# Rpi-CAN.net
KiCad netlist of a schematic drawn in EAGLE
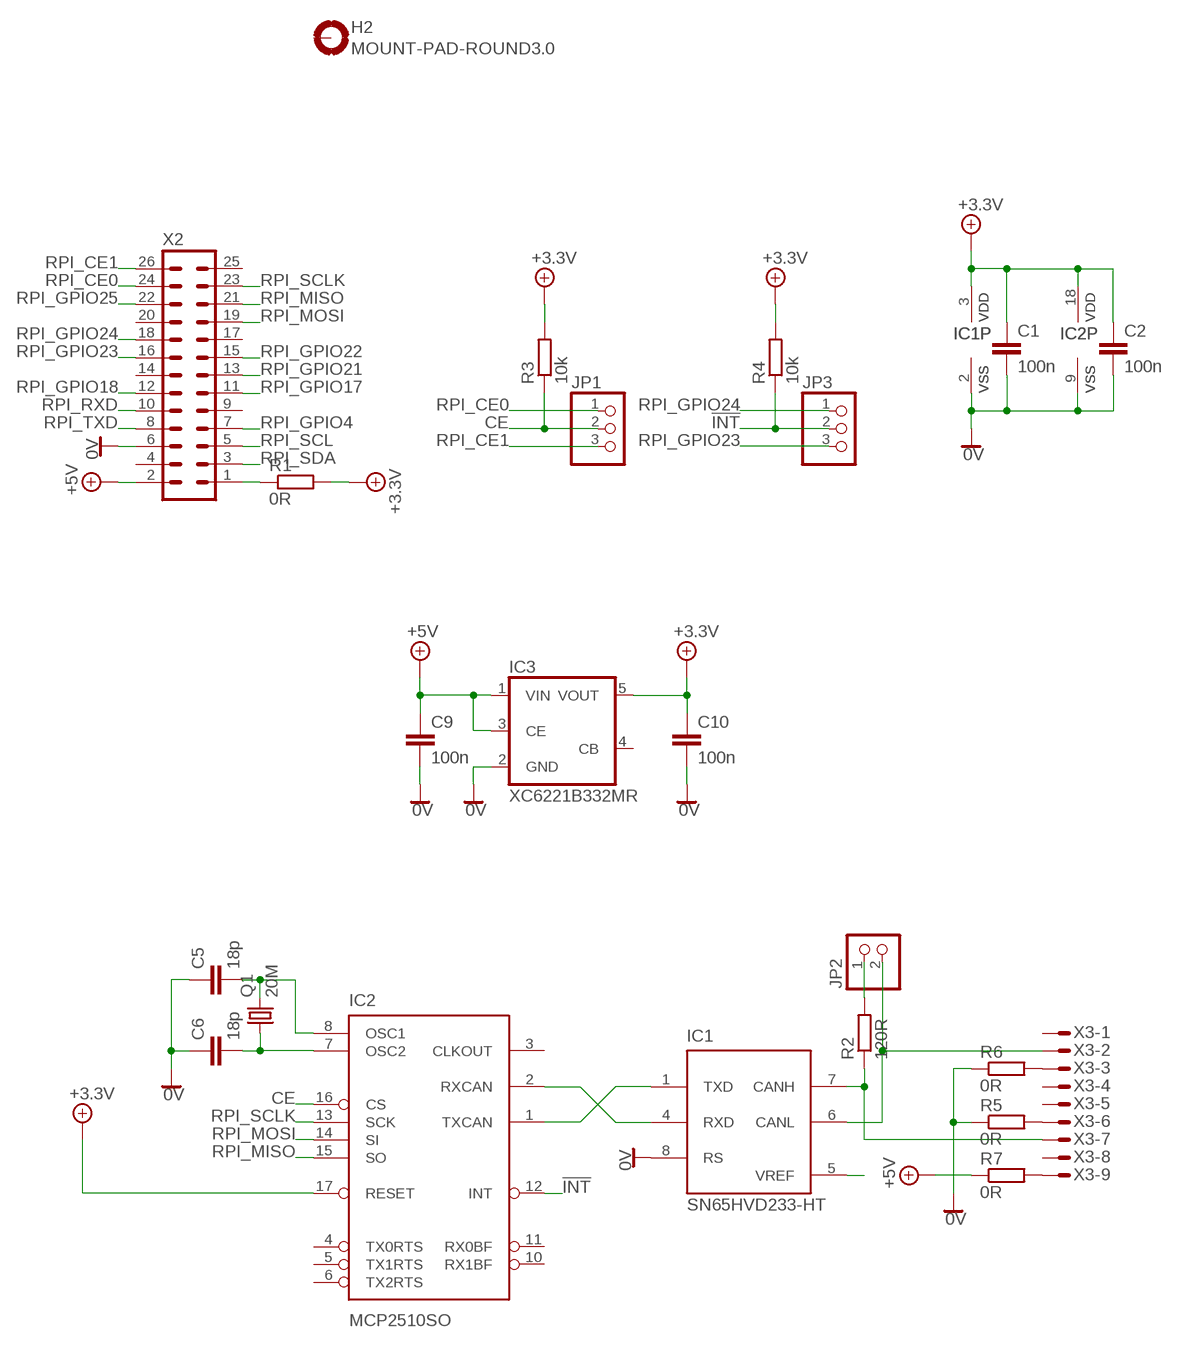
[diagram p0: schematic, sheet 1]

(export (version "E")
  (design (tool "Eeschema 10.0.6"))
  (components
    (comp (ref "C1")
      (value "100n")
      (footprint "eagle-import:C0805")
      (libsource (lib "eagle-import") (part "C-EUC0805"))
    )
    (comp (ref "C2")
      (value "100n")
      (footprint "eagle-import:C0805")
      (libsource (lib "eagle-import") (part "C-EUC0805"))
    )
    (comp (ref "C5")
      (value "18p")
      (footprint "eagle-import:C0805")
      (libsource (lib "eagle-import") (part "C-EUC0805"))
    )
    (comp (ref "C6")
      (value "18p")
      (footprint "eagle-import:C0805")
      (libsource (lib "eagle-import") (part "C-EUC0805"))
    )
    (comp (ref "C9")
      (value "100n")
      (footprint "eagle-import:C0805")
      (libsource (lib "eagle-import") (part "C-EUC0805"))
    )
    (comp (ref "C10")
      (value "100n")
      (footprint "eagle-import:C0805")
      (libsource (lib "eagle-import") (part "C-EUC0805"))
    )
    (comp (ref "H2")
      (value "MOUNT-PAD-ROUND3.0")
      (footprint "eagle-import:3,0-PAD")
      (libsource (lib "eagle-import") (part "MOUNT-PAD-ROUND3.0"))
    )
    (comp (ref "IC1")
      (value "SN65HVD233-HT")
      (footprint "eagle-import:SO-08")
      (libsource (lib "eagle-import") (part "MCP2551SN"))
    )
    (comp (ref "IC2")
      (value "MCP2510SO")
      (footprint "eagle-import:SO-18W")
      (libsource (lib "eagle-import") (part "MCP2510SO"))
    )
    (comp (ref "IC3")
      (value "XC6221B332MR")
      (footprint "eagle-import:SOT25")
      (libsource (lib "eagle-import") (part "TS520533"))
    )
    (comp (ref "JP1")
      (value "PINHD-1X3")
      (footprint "eagle-import:1X03")
      (libsource (lib "eagle-import") (part "PINHD-1X3"))
    )
    (comp (ref "JP2")
      (value "PINHD-1X2")
      (footprint "eagle-import:1X02")
      (libsource (lib "eagle-import") (part "PINHD-1X2"))
    )
    (comp (ref "JP3")
      (value "PINHD-1X3")
      (footprint "eagle-import:1X03")
      (libsource (lib "eagle-import") (part "PINHD-1X3"))
    )
    (comp (ref "Q1")
      (value "20M")
      (footprint "eagle-import:SM49")
      (libsource (lib "eagle-import") (part "CRYSTALSM49"))
    )
    (comp (ref "R1")
      (value "0R")
      (footprint "eagle-import:R0805")
      (libsource (lib "eagle-import") (part "R-EU_R0805"))
    )
    (comp (ref "R2")
      (value "120R")
      (footprint "eagle-import:R0805")
      (libsource (lib "eagle-import") (part "R-EU_R0805"))
    )
    (comp (ref "R3")
      (value "10k")
      (footprint "eagle-import:R0805")
      (libsource (lib "eagle-import") (part "R-EU_R0805"))
    )
    (comp (ref "R4")
      (value "10k")
      (footprint "eagle-import:R0805")
      (libsource (lib "eagle-import") (part "R-EU_R0805"))
    )
    (comp (ref "R5")
      (value "0R")
      (footprint "eagle-import:R0805")
      (libsource (lib "eagle-import") (part "R-EU_R0805"))
    )
    (comp (ref "R6")
      (value "0R")
      (footprint "eagle-import:R0805")
      (libsource (lib "eagle-import") (part "R-EU_R0805"))
    )
    (comp (ref "R7")
      (value "0R")
      (footprint "eagle-import:R0805")
      (libsource (lib "eagle-import") (part "R-EU_R0805"))
    )
    (comp (ref "X2")
      (value "MA13-2")
      (footprint "eagle-import:MA13-2")
      (libsource (lib "eagle-import") (part "MA13-2"))
    )
    (comp (ref "X3")
      (value "M09DS")
      (footprint "eagle-import:M09D")
      (libsource (lib "eagle-import") (part "M09?SD"))
    )
  )
  (nets
    (net (code "1") (name "+3.3V") (class "Default")
      (node (ref "C1") (pin "1") (pinfunction "1_1") (pintype "passive"))
      (node (ref "C10") (pin "1") (pinfunction "1_1") (pintype "passive"))
      (node (ref "C2") (pin "1") (pinfunction "1_1") (pintype "passive"))
      (node (ref "IC1") (pin "3") (pinfunction "VDD_3") (pintype "power_in"))
      (node (ref "IC2") (pin "17") (pinfunction "RESET_17") (pintype "input"))
      (node (ref "IC2") (pin "18") (pinfunction "VDD_18") (pintype "power_in"))
      (node (ref "IC3") (pin "5") (pinfunction "VOUT_5") (pintype "passive"))
      (node (ref "R1") (pin "2") (pinfunction "2_2") (pintype "passive"))
      (node (ref "R3") (pin "2") (pinfunction "2_2") (pintype "passive"))
      (node (ref "R4") (pin "2") (pinfunction "2_2") (pintype "passive"))
    )
    (net (code "2") (name "+5V") (class "Default")
      (node (ref "C9") (pin "1") (pinfunction "1_1") (pintype "passive"))
      (node (ref "IC3") (pin "1") (pinfunction "VIN_1") (pintype "input"))
      (node (ref "IC3") (pin "3") (pinfunction "CE_3") (pintype "input"))
      (node (ref "R7") (pin "1") (pinfunction "1_1") (pintype "passive"))
      (node (ref "X2") (pin "2") (pinfunction "2_2") (pintype "passive"))
    )
    (net (code "3") (name "/CE") (class "Default")
      (node (ref "IC2") (pin "16") (pinfunction "CS_16") (pintype "input"))
      (node (ref "JP1") (pin "2") (pinfunction "2_2") (pintype "passive"))
      (node (ref "R3") (pin "1") (pinfunction "1_1") (pintype "passive"))
    )
    (net (code "4") (name "/RPI_CE0") (class "Default")
      (node (ref "JP1") (pin "1") (pinfunction "1_1") (pintype "passive"))
      (node (ref "X2") (pin "24") (pinfunction "24_24") (pintype "passive"))
    )
    (net (code "5") (name "/RPI_CE1") (class "Default")
      (node (ref "JP1") (pin "3") (pinfunction "3_3") (pintype "passive"))
      (node (ref "X2") (pin "26") (pinfunction "26_26") (pintype "passive"))
    )
    (net (code "6") (name "/RPI_GPIO4") (class "Default")
      (node (ref "X2") (pin "7") (pinfunction "7_7") (pintype "passive"))
    )
    (net (code "7") (name "/RPI_GPIO17") (class "Default")
      (node (ref "X2") (pin "11") (pinfunction "11_11") (pintype "passive"))
    )
    (net (code "8") (name "/RPI_GPIO18") (class "Default")
      (node (ref "X2") (pin "12") (pinfunction "12_12") (pintype "passive"))
    )
    (net (code "9") (name "/RPI_GPIO21") (class "Default")
      (node (ref "X2") (pin "13") (pinfunction "13_13") (pintype "passive"))
    )
    (net (code "10") (name "/RPI_GPIO22") (class "Default")
      (node (ref "X2") (pin "15") (pinfunction "15_15") (pintype "passive"))
    )
    (net (code "11") (name "/RPI_GPIO23") (class "Default")
      (node (ref "JP3") (pin "3") (pinfunction "3_3") (pintype "passive"))
      (node (ref "X2") (pin "16") (pinfunction "16_16") (pintype "passive"))
    )
    (net (code "12") (name "/RPI_GPIO24") (class "Default")
      (node (ref "JP3") (pin "1") (pinfunction "1_1") (pintype "passive"))
      (node (ref "X2") (pin "18") (pinfunction "18_18") (pintype "passive"))
    )
    (net (code "13") (name "/RPI_GPIO25") (class "Default")
      (node (ref "X2") (pin "22") (pinfunction "22_22") (pintype "passive"))
    )
    (net (code "14") (name "/RPI_MISO") (class "Default")
      (node (ref "IC2") (pin "15") (pinfunction "SO_15") (pintype "output"))
      (node (ref "X2") (pin "21") (pinfunction "21_21") (pintype "passive"))
    )
    (net (code "15") (name "/RPI_MOSI") (class "Default")
      (node (ref "IC2") (pin "14") (pinfunction "SI_14") (pintype "input"))
      (node (ref "X2") (pin "19") (pinfunction "19_19") (pintype "passive"))
    )
    (net (code "16") (name "/RPI_RXD") (class "Default")
      (node (ref "X2") (pin "10") (pinfunction "10_10") (pintype "passive"))
    )
    (net (code "17") (name "/RPI_SCL") (class "Default")
      (node (ref "X2") (pin "5") (pinfunction "5_5") (pintype "passive"))
    )
    (net (code "18") (name "/RPI_SCLK") (class "Default")
      (node (ref "IC2") (pin "13") (pinfunction "SCK_13") (pintype "input"))
      (node (ref "X2") (pin "23") (pinfunction "23_23") (pintype "passive"))
    )
    (net (code "19") (name "/RPI_SDA") (class "Default")
      (node (ref "X2") (pin "3") (pinfunction "3_3") (pintype "passive"))
    )
    (net (code "20") (name "/RPI_TXD") (class "Default")
      (node (ref "X2") (pin "8") (pinfunction "8_8") (pintype "passive"))
    )
    (net (code "21") (name "/~{INT}") (class "Default")
      (node (ref "IC2") (pin "12") (pinfunction "INT_12") (pintype "output"))
      (node (ref "JP3") (pin "2") (pinfunction "2_2") (pintype "passive"))
      (node (ref "R4") (pin "1") (pinfunction "1_1") (pintype "passive"))
    )
    (net (code "22") (name "0V") (class "Default")
      (node (ref "C1") (pin "2") (pinfunction "2_2") (pintype "passive"))
      (node (ref "C10") (pin "2") (pinfunction "2_2") (pintype "passive"))
      (node (ref "C2") (pin "2") (pinfunction "2_2") (pintype "passive"))
      (node (ref "C5") (pin "1") (pinfunction "1_1") (pintype "passive"))
      (node (ref "C6") (pin "1") (pinfunction "1_1") (pintype "passive"))
      (node (ref "C9") (pin "2") (pinfunction "2_2") (pintype "passive"))
      (node (ref "IC1") (pin "2") (pinfunction "VSS_2") (pintype "power_in"))
      (node (ref "IC1") (pin "8") (pinfunction "RS_8") (pintype "input"))
      (node (ref "IC2") (pin "9") (pinfunction "VSS_9") (pintype "power_in"))
      (node (ref "IC3") (pin "2") (pinfunction "GND_2") (pintype "passive"))
      (node (ref "R5") (pin "1") (pinfunction "1_1") (pintype "passive"))
      (node (ref "R6") (pin "1") (pinfunction "1_1") (pintype "passive"))
      (node (ref "X2") (pin "6") (pinfunction "6_6") (pintype "passive"))
    )
    (net (code "23") (name "Net-(IC1A-CANH)") (class "Default")
      (node (ref "IC1") (pin "7") (pinfunction "CANH_7") (pintype "bidirectional"))
      (node (ref "R2") (pin "1") (pinfunction "1_1") (pintype "passive"))
      (node (ref "X3") (pin "7") (pinfunction "M_7") (pintype "passive"))
    )
    (net (code "24") (name "Net-(IC1A-CANL)") (class "Default")
      (node (ref "IC1") (pin "6") (pinfunction "CANL_6") (pintype "bidirectional"))
      (node (ref "JP2") (pin "2") (pinfunction "2_2") (pintype "passive"))
      (node (ref "X3") (pin "2") (pinfunction "M_2") (pintype "passive"))
    )
    (net (code "25") (name "Net-(IC1A-RXD)") (class "Default")
      (node (ref "IC1") (pin "4") (pinfunction "RXD_4") (pintype "output"))
      (node (ref "IC2") (pin "2") (pinfunction "RXCAN_2") (pintype "input"))
    )
    (net (code "26") (name "Net-(IC1A-TXD)") (class "Default")
      (node (ref "IC1") (pin "1") (pinfunction "TXD_1") (pintype "input"))
      (node (ref "IC2") (pin "1") (pinfunction "TXCAN_1") (pintype "output"))
    )
    (net (code "27") (name "Net-(IC2A-OSC1)") (class "Default")
      (node (ref "C5") (pin "2") (pinfunction "2_2") (pintype "passive"))
      (node (ref "IC2") (pin "8") (pinfunction "OSC1_8") (pintype "input"))
      (node (ref "Q1") (pin "2") (pinfunction "2_2") (pintype "passive"))
    )
    (net (code "28") (name "Net-(IC2A-OSC2)") (class "Default")
      (node (ref "C6") (pin "2") (pinfunction "2_2") (pintype "passive"))
      (node (ref "IC2") (pin "7") (pinfunction "OSC2_7") (pintype "output"))
      (node (ref "Q1") (pin "1") (pinfunction "1_1") (pintype "passive"))
    )
    (net (code "29") (name "Net-(JP2-Pad1)") (class "Default")
      (node (ref "JP2") (pin "1") (pinfunction "1_1") (pintype "passive"))
      (node (ref "R2") (pin "2") (pinfunction "2_2") (pintype "passive"))
    )
    (net (code "30") (name "Net-(R1-Pad1)") (class "Default")
      (node (ref "R1") (pin "1") (pinfunction "1_1") (pintype "passive"))
      (node (ref "X2") (pin "1") (pinfunction "1_1") (pintype "passive"))
    )
    (net (code "31") (name "Net-(X3C-M)") (class "Default")
      (node (ref "R6") (pin "2") (pinfunction "2_2") (pintype "passive"))
      (node (ref "X3") (pin "3") (pinfunction "M_3") (pintype "passive"))
    )
    (net (code "32") (name "Net-(X3F-M)") (class "Default")
      (node (ref "R5") (pin "2") (pinfunction "2_2") (pintype "passive"))
      (node (ref "X3") (pin "6") (pinfunction "M_6") (pintype "passive"))
    )
    (net (code "33") (name "Net-(X3I-M)") (class "Default")
      (node (ref "R7") (pin "2") (pinfunction "2_2") (pintype "passive"))
      (node (ref "X3") (pin "9") (pinfunction "M_9") (pintype "passive"))
    )
    (net (code "34") (name "unconnected-(H2-MOUNT-PadB3,0)") (class "Default")
      (node (ref "H2") (pin "B3,0") (pinfunction "MOUNT_B3,0") (pintype "passive"))
    )
    (net (code "35") (name "unconnected-(IC1A-VREF-Pad5)") (class "Default")
      (node (ref "IC1") (pin "5") (pinfunction "VREF_5") (pintype "power_in"))
    )
    (net (code "36") (name "unconnected-(IC2A-CLKOUT-Pad3)") (class "Default")
      (node (ref "IC2") (pin "3") (pinfunction "CLKOUT_3") (pintype "output"))
    )
    (net (code "37") (name "unconnected-(IC2A-RX0BF-Pad11)") (class "Default")
      (node (ref "IC2") (pin "11") (pinfunction "RX0BF_11") (pintype "output"))
    )
    (net (code "38") (name "unconnected-(IC2A-RX1BF-Pad10)") (class "Default")
      (node (ref "IC2") (pin "10") (pinfunction "RX1BF_10") (pintype "output"))
    )
    (net (code "39") (name "unconnected-(IC2A-TX0RTS-Pad4)") (class "Default")
      (node (ref "IC2") (pin "4") (pinfunction "TX0RTS_4") (pintype "input"))
    )
    (net (code "40") (name "unconnected-(IC2A-TX1RTS-Pad5)") (class "Default")
      (node (ref "IC2") (pin "5") (pinfunction "TX1RTS_5") (pintype "input"))
    )
    (net (code "41") (name "unconnected-(IC2A-TX2RTS-Pad6)") (class "Default")
      (node (ref "IC2") (pin "6") (pinfunction "TX2RTS_6") (pintype "input"))
    )
    (net (code "42") (name "unconnected-(IC3-CB-Pad4)") (class "Default")
      (node (ref "IC3") (pin "4") (pinfunction "CB_4") (pintype "input"))
    )
    (net (code "43") (name "unconnected-(X2-Pad4)") (class "Default")
      (node (ref "X2") (pin "4") (pinfunction "4_4") (pintype "passive"))
    )
    (net (code "44") (name "unconnected-(X2-Pad9)") (class "Default")
      (node (ref "X2") (pin "9") (pinfunction "9_9") (pintype "passive"))
    )
    (net (code "45") (name "unconnected-(X2-Pad14)") (class "Default")
      (node (ref "X2") (pin "14") (pinfunction "14_14") (pintype "passive"))
    )
    (net (code "46") (name "unconnected-(X2-Pad17)") (class "Default")
      (node (ref "X2") (pin "17") (pinfunction "17_17") (pintype "passive"))
    )
    (net (code "47") (name "unconnected-(X2-Pad20)") (class "Default")
      (node (ref "X2") (pin "20") (pinfunction "20_20") (pintype "passive"))
    )
    (net (code "48") (name "unconnected-(X2-Pad25)") (class "Default")
      (node (ref "X2") (pin "25") (pinfunction "25_25") (pintype "passive"))
    )
    (net (code "49") (name "unconnected-(X3A-M-Pad1)") (class "Default")
      (node (ref "X3") (pin "1") (pinfunction "M_1") (pintype "passive"))
    )
    (net (code "50") (name "unconnected-(X3D-M-Pad4)") (class "Default")
      (node (ref "X3") (pin "4") (pinfunction "M_4") (pintype "passive"))
    )
    (net (code "51") (name "unconnected-(X3E-M-Pad5)") (class "Default")
      (node (ref "X3") (pin "5") (pinfunction "M_5") (pintype "passive"))
    )
    (net (code "52") (name "unconnected-(X3H-M-Pad8)") (class "Default")
      (node (ref "X3") (pin "8") (pinfunction "M_8") (pintype "passive"))
    )
  )
)
